# SCH_Display_Altium.net
KiCad netlist of a schematic drawn in Altium Designer
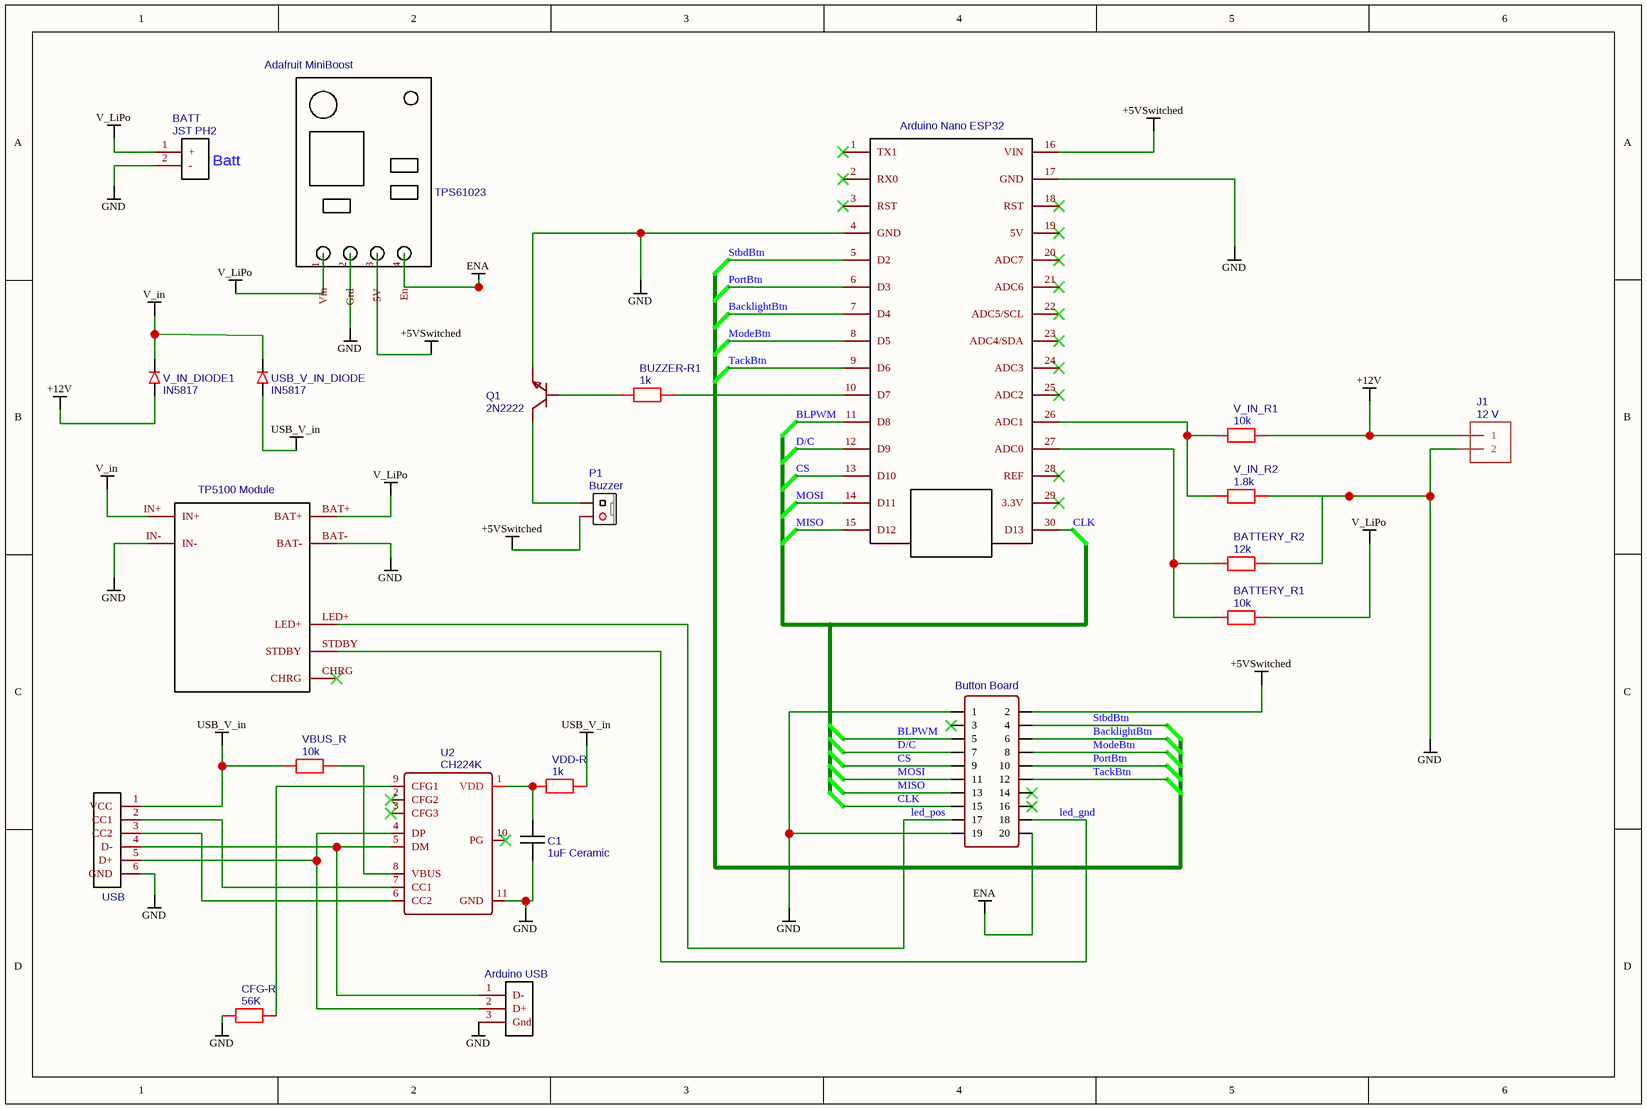
[diagram p0: SCH_Display_Altium.schdoc]

(export (version "E")
  (design (tool "Eeschema 10.0.6"))
  (components
    (comp (ref "BATT")
      (value "JST PH2")
      (fields (field (name "CONTRIBUTOR") "pwarrow99"))
      (libsource (lib "altium-import") (part "root_0_JST PH2_"))
    )
    (comp (ref "BATTERY_R1")
      (value "10k")
      (fields (field (name "CONTRIBUTOR") "Kagutsuchi"))
      (libsource (lib "altium-import") (part "root_0_10k_"))
    )
    (comp (ref "BATTERY_R2")
      (value "12k")
      (fields (field (name "CONTRIBUTOR") "Kagutsuchi"))
      (libsource (lib "altium-import") (part "root_0_12k_"))
    )
    (comp (ref "BUTTON_LED1")
      (value "Button Board")
      (fields (field (name "CONTRIBUTOR") "LCEDA_Lib"))
      (libsource (lib "altium-import") (part "root_0_Button Board_"))
    )
    (comp (ref "BUZZER-R1")
      (value "1k")
      (fields (field (name "CONTRIBUTOR") "Kagutsuchi"))
      (libsource (lib "altium-import") (part "root_0_1k_"))
    )
    (comp (ref "C1")
      (value "1uF Ceramic")
      (fields
        (field (name "MANUFACTURER PART") "Capacitor_Ceramic")
        (field (name "CONTRIBUTOR") "huuvinhz755")
      )
      (libsource (lib "altium-import") (part "root_3_1uF Ceramic_"))
    )
    (comp (ref "CFG-R")
      (value "56K")
      (fields (field (name "CONTRIBUTOR") "Kagutsuchi"))
      (libsource (lib "altium-import") (part "root_0_56K_"))
    )
    (comp (ref "J1")
      (value "12 V")
      (fields (field (name "CONTRIBUTOR") "Adafruit"))
      (libsource (lib "altium-import") (part "root_0_12 V_"))
    )
    (comp (ref "JST-PH-2.0_1X6")
      (value "USB")
      (fields (field (name "MANUFACTURER PART") "JST-PH-2.0_1x6") (field (name "CONTRIBUTOR") "yury26nev"))
      (libsource (lib "altium-import") (part "root_0_USB_"))
    )
    (comp (ref "JST_XH_1X3")
      (value "Arduino USB")
      (fields (field (name "CONTRIBUTOR") "GeMeMe"))
      (libsource (lib "altium-import") (part "root_0_Arduino USB_"))
    )
    (comp (ref "P1")
      (value "Buzzer")
      (fields
        (field (name "MANUFACTURER PART") "Headers  Pins2.54mm1*10P")
        (field (name "CONTRIBUTOR") "jousterde1")
      )
      (libsource (lib "altium-import") (part "root_0_Buzzer_"))
    )
    (comp (ref "Q1")
      (value "2N2222")
      (fields
        (field (name "MANUFACTURER") "ST(先科)")
        (field (name "MANUFACTURER PART") "2N2222A")
        (field (name "CONTRIBUTOR") "LCSC")
      )
      (libsource (lib "altium-import") (part "root_2_2N2222_"))
    )
    (comp (ref "TPS61023")
      (value "Adafruit MiniBoost")
      (fields (field (name "CONTRIBUTOR") "jefflorditch"))
      (libsource (lib "altium-import") (part "root_0_Adafruit MiniBoost_"))
    )
    (comp (ref "U1")
      (value "Arduino Nano ESP32")
      (fields (field (name "CONTRIBUTOR") "Nikolay Yanev"))
      (libsource (lib "altium-import") (part "root_0_Arduino Nano ESP32_"))
    )
    (comp (ref "U2")
      (value "CH224K")
      (fields (field (name "MANUFACTURER") "WCH(南京沁恒)") (field (name "CONTRIBUTOR") "lcsc"))
      (libsource (lib "altium-import") (part "root_0_CH224K_"))
    )
    (comp (ref "U3")
      (value "TP5100 Module")
      (fields (field (name "MANUFACTURER PART") "TP5100-MODULE") (field (name "CONTRIBUTOR") "cropemail"))
      (libsource (lib "altium-import") (part "root_0_TP5100 Module_"))
    )
    (comp (ref "USB_V_IN_DIODE")
      (value "IN5817")
      (fields (field (name "MANUFACTURER PART") "DIODE") (field (name "CONTRIBUTOR") "mimit.oscar"))
      (libsource (lib "altium-import") (part "root_1_IN5817_"))
    )
    (comp (ref "VBUS_R")
      (value "10k")
      (fields (field (name "CONTRIBUTOR") "Kagutsuchi"))
      (libsource (lib "altium-import") (part "root_0_10k_"))
    )
    (comp (ref "VDD-R")
      (value "1k")
      (fields (field (name "CONTRIBUTOR") "Kagutsuchi"))
      (libsource (lib "altium-import") (part "root_0_1k_"))
    )
    (comp (ref "V_IN_DIODE1")
      (value "IN5817")
      (fields (field (name "MANUFACTURER PART") "DIODE") (field (name "CONTRIBUTOR") "mimit.oscar"))
      (libsource (lib "altium-import") (part "root_1_IN5817_"))
    )
    (comp (ref "V_IN_R1")
      (value "10k")
      (fields (field (name "CONTRIBUTOR") "Kagutsuchi"))
      (libsource (lib "altium-import") (part "root_0_10k_"))
    )
    (comp (ref "V_IN_R2")
      (value "1.8k")
      (fields (field (name "CONTRIBUTOR") "Kagutsuchi"))
      (libsource (lib "altium-import") (part "root_0_1.8k_"))
    )
  )
  (nets
    (net (code "1") (name "+5VSwitched") (class "Default")
      (node (ref "BUTTON_LED1") (pin "2") (pinfunction "2_2") (pintype "passive"))
      (node (ref "P1") (pin "2") (pinfunction "2_2") (pintype "passive"))
      (node (ref "TPS61023") (pin "3") (pinfunction "5V_3") (pintype "passive"))
      (node (ref "U1") (pin "16") (pinfunction "VIN_16") (pintype "passive"))
    )
    (net (code "2") (name "+12V") (class "Default")
      (node (ref "J1") (pin "1") (pinfunction "1_1") (pintype "passive"))
      (node (ref "V_IN_DIODE1") (pin "1") (pinfunction "1_1") (pintype "passive"))
      (node (ref "V_IN_R1") (pin "2") (pinfunction "1_2") (pintype "passive"))
    )
    (net (code "3") (name "/BLPWM") (class "Default")
      (node (ref "BUTTON_LED1") (pin "5") (pinfunction "5_5") (pintype "passive"))
      (node (ref "U1") (pin "11") (pinfunction "D8_11") (pintype "passive"))
    )
    (net (code "4") (name "/BacklightBtn") (class "Default")
      (node (ref "BUTTON_LED1") (pin "6") (pinfunction "6_6") (pintype "passive"))
      (node (ref "U1") (pin "7") (pinfunction "D4_7") (pintype "passive"))
    )
    (net (code "5") (name "/CLK") (class "Default")
      (node (ref "BUTTON_LED1") (pin "15") (pinfunction "15_15") (pintype "passive"))
      (node (ref "U1") (pin "30") (pinfunction "D13_30") (pintype "passive"))
    )
    (net (code "6") (name "/CS") (class "Default")
      (node (ref "BUTTON_LED1") (pin "9") (pinfunction "9_9") (pintype "passive"))
      (node (ref "U1") (pin "13") (pinfunction "D10_13") (pintype "passive"))
    )
    (net (code "7") (name "/D{slash}C") (class "Default")
      (node (ref "BUTTON_LED1") (pin "7") (pinfunction "7_7") (pintype "passive"))
      (node (ref "U1") (pin "12") (pinfunction "D9_12") (pintype "passive"))
    )
    (net (code "8") (name "/MISO") (class "Default")
      (node (ref "BUTTON_LED1") (pin "13") (pinfunction "13_13") (pintype "passive"))
      (node (ref "U1") (pin "15") (pinfunction "D12_15") (pintype "passive"))
    )
    (net (code "9") (name "/MOSI") (class "Default")
      (node (ref "BUTTON_LED1") (pin "11") (pinfunction "11_11") (pintype "passive"))
      (node (ref "U1") (pin "14") (pinfunction "D11_14") (pintype "passive"))
    )
    (net (code "10") (name "/ModeBtn") (class "Default")
      (node (ref "BUTTON_LED1") (pin "8") (pinfunction "8_8") (pintype "passive"))
      (node (ref "U1") (pin "8") (pinfunction "D5_8") (pintype "passive"))
    )
    (net (code "11") (name "/PortBtn") (class "Default")
      (node (ref "BUTTON_LED1") (pin "10") (pinfunction "10_10") (pintype "passive"))
      (node (ref "U1") (pin "6") (pinfunction "D3_6") (pintype "passive"))
    )
    (net (code "12") (name "/StbdBtn") (class "Default")
      (node (ref "BUTTON_LED1") (pin "4") (pinfunction "4_4") (pintype "passive"))
      (node (ref "U1") (pin "5") (pinfunction "D2_5") (pintype "passive"))
    )
    (net (code "13") (name "/TackBtn") (class "Default")
      (node (ref "BUTTON_LED1") (pin "12") (pinfunction "12_12") (pintype "passive"))
      (node (ref "U1") (pin "9") (pinfunction "D6_9") (pintype "passive"))
    )
    (net (code "14") (name "/led_gnd") (class "Default")
      (node (ref "BUTTON_LED1") (pin "18") (pinfunction "18_18") (pintype "passive"))
      (node (ref "U3") (pin "STDBY") (pinfunction "STDBY_STDBY") (pintype "passive"))
    )
    (net (code "15") (name "/led_pos") (class "Default")
      (node (ref "BUTTON_LED1") (pin "17") (pinfunction "17_17") (pintype "passive"))
      (node (ref "U3") (pin "LED+") (pinfunction "LED+_LED+") (pintype "passive"))
    )
    (net (code "16") (name "ENA") (class "Default")
      (node (ref "BUTTON_LED1") (pin "20") (pinfunction "20_20") (pintype "passive"))
      (node (ref "TPS61023") (pin "4") (pinfunction "En_4") (pintype "passive"))
    )
    (net (code "17") (name "GND") (class "Default")
      (node (ref "BATT") (pin "2") (pinfunction "-_2") (pintype "passive"))
      (node (ref "BATTERY_R2") (pin "2") (pinfunction "1_2") (pintype "passive"))
      (node (ref "BUTTON_LED1") (pin "1") (pinfunction "1_1") (pintype "passive"))
      (node (ref "BUTTON_LED1") (pin "19") (pinfunction "19_19") (pintype "passive"))
      (node (ref "C1") (pin "2") (pinfunction "2_2") (pintype "passive"))
      (node (ref "CFG-R") (pin "1") (pinfunction "2_1") (pintype "passive"))
      (node (ref "J1") (pin "2") (pinfunction "2_2") (pintype "passive"))
      (node (ref "JST-PH-2.0_1X6") (pin "6") (pinfunction "GND_6") (pintype "passive"))
      (node (ref "JST_XH_1X3") (pin "3") (pinfunction "Gnd_3") (pintype "passive"))
      (node (ref "Q1") (pin "1") (pinfunction "E_1") (pintype "passive"))
      (node (ref "TPS61023") (pin "2") (pinfunction "Grd_2") (pintype "passive"))
      (node (ref "U1") (pin "17") (pinfunction "GND_17") (pintype "passive"))
      (node (ref "U1") (pin "4") (pinfunction "GND_4") (pintype "passive"))
      (node (ref "U2") (pin "11") (pinfunction "GND_11") (pintype "passive"))
      (node (ref "U3") (pin "BAT-") (pinfunction "BAT-_BAT-") (pintype "passive"))
      (node (ref "U3") (pin "IN-") (pinfunction "IN-_IN-") (pintype "passive"))
      (node (ref "V_IN_R2") (pin "2") (pinfunction "1_2") (pintype "passive"))
    )
    (net (code "18") (name "Net-(BATTERY_R1-2)") (class "Default")
      (node (ref "BATTERY_R1") (pin "1") (pinfunction "2_1") (pintype "passive"))
      (node (ref "BATTERY_R2") (pin "1") (pinfunction "2_1") (pintype "passive"))
      (node (ref "U1") (pin "27") (pinfunction "ADC0_27") (pintype "passive"))
    )
    (net (code "19") (name "Net-(BUZZER-R1-1)") (class "Default")
      (node (ref "BUZZER-R1") (pin "2") (pinfunction "1_2") (pintype "passive"))
      (node (ref "U1") (pin "10") (pinfunction "D7_10") (pintype "passive"))
    )
    (net (code "20") (name "Net-(BUZZER-R1-2)") (class "Default")
      (node (ref "BUZZER-R1") (pin "1") (pinfunction "2_1") (pintype "passive"))
      (node (ref "Q1") (pin "2") (pinfunction "B_2") (pintype "passive"))
    )
    (net (code "21") (name "Net-(CFG-R-1)") (class "Default")
      (node (ref "CFG-R") (pin "2") (pinfunction "1_2") (pintype "passive"))
      (node (ref "U2") (pin "9") (pinfunction "CFG1_9") (pintype "passive"))
    )
    (net (code "22") (name "Net-(JST-PH-2.0_1X6-CC1)") (class "Default")
      (node (ref "JST-PH-2.0_1X6") (pin "2") (pinfunction "CC1_2") (pintype "passive"))
      (node (ref "U2") (pin "7") (pinfunction "CC1_7") (pintype "passive"))
    )
    (net (code "23") (name "Net-(JST-PH-2.0_1X6-CC2)") (class "Default")
      (node (ref "JST-PH-2.0_1X6") (pin "3") (pinfunction "CC2_3") (pintype "passive"))
      (node (ref "U2") (pin "6") (pinfunction "CC2_6") (pintype "passive"))
    )
    (net (code "24") (name "Net-(JST-PH-2.0_1X6-D+)") (class "Default")
      (node (ref "JST-PH-2.0_1X6") (pin "5") (pinfunction "D+_5") (pintype "passive"))
      (node (ref "JST_XH_1X3") (pin "2") (pinfunction "D+_2") (pintype "passive"))
      (node (ref "U2") (pin "4") (pinfunction "DP_4") (pintype "passive"))
    )
    (net (code "25") (name "Net-(JST-PH-2.0_1X6-D-)") (class "Default")
      (node (ref "JST-PH-2.0_1X6") (pin "4") (pinfunction "D-_4") (pintype "passive"))
      (node (ref "JST_XH_1X3") (pin "1") (pinfunction "D-_1") (pintype "passive"))
      (node (ref "U2") (pin "5") (pinfunction "DM_5") (pintype "passive"))
    )
    (net (code "26") (name "Net-(Q1-C)") (class "Default")
      (node (ref "P1") (pin "1") (pinfunction "1_1") (pintype "passive"))
      (node (ref "Q1") (pin "3") (pinfunction "C_3") (pintype "passive"))
    )
    (net (code "27") (name "Net-(U1-ADC1)") (class "Default")
      (node (ref "U1") (pin "26") (pinfunction "ADC1_26") (pintype "passive"))
      (node (ref "V_IN_R1") (pin "1") (pinfunction "2_1") (pintype "passive"))
      (node (ref "V_IN_R2") (pin "1") (pinfunction "2_1") (pintype "passive"))
    )
    (net (code "28") (name "Net-(U2-VBUS)") (class "Default")
      (node (ref "U2") (pin "8") (pinfunction "VBUS_8") (pintype "passive"))
      (node (ref "VBUS_R") (pin "2") (pinfunction "1_2") (pintype "passive"))
    )
    (net (code "29") (name "Net-(U2-VDD)") (class "Default")
      (node (ref "C1") (pin "1") (pinfunction "1_1") (pintype "passive"))
      (node (ref "U2") (pin "1") (pinfunction "VDD_1") (pintype "passive"))
      (node (ref "VDD-R") (pin "1") (pinfunction "2_1") (pintype "passive"))
    )
    (net (code "30") (name "USB_V_in") (class "Default")
      (node (ref "JST-PH-2.0_1X6") (pin "1") (pinfunction "VCC_1") (pintype "passive"))
      (node (ref "USB_V_IN_DIODE") (pin "1") (pinfunction "1_1") (pintype "passive"))
      (node (ref "VBUS_R") (pin "1") (pinfunction "2_1") (pintype "passive"))
      (node (ref "VDD-R") (pin "2") (pinfunction "1_2") (pintype "passive"))
    )
    (net (code "31") (name "V_LiPo") (class "Default")
      (node (ref "BATT") (pin "1") (pinfunction "+_1") (pintype "passive"))
      (node (ref "BATTERY_R1") (pin "2") (pinfunction "1_2") (pintype "passive"))
      (node (ref "TPS61023") (pin "1") (pinfunction "Vin_1") (pintype "passive"))
      (node (ref "U3") (pin "BAT+") (pinfunction "BAT+_BAT+") (pintype "passive"))
    )
    (net (code "32") (name "V_in") (class "Default")
      (node (ref "U3") (pin "IN+") (pinfunction "IN+_IN+") (pintype "passive"))
      (node (ref "USB_V_IN_DIODE") (pin "2") (pinfunction "2_2") (pintype "passive"))
      (node (ref "V_IN_DIODE1") (pin "2") (pinfunction "2_2") (pintype "passive"))
    )
    (net (code "33") (name "unconnected-(BUTTON_LED1-Pad3)") (class "Default")
      (node (ref "BUTTON_LED1") (pin "3") (pinfunction "3_3") (pintype "passive+no_connect"))
    )
    (net (code "34") (name "unconnected-(BUTTON_LED1-Pad14)") (class "Default")
      (node (ref "BUTTON_LED1") (pin "14") (pinfunction "14_14") (pintype "passive+no_connect"))
    )
    (net (code "35") (name "unconnected-(BUTTON_LED1-Pad16)") (class "Default")
      (node (ref "BUTTON_LED1") (pin "16") (pinfunction "16_16") (pintype "passive+no_connect"))
    )
    (net (code "36") (name "unconnected-(U1-3.3V-Pad29)") (class "Default")
      (node (ref "U1") (pin "29") (pinfunction "3.3V_29") (pintype "passive+no_connect"))
    )
    (net (code "37") (name "unconnected-(U1-5V-Pad19)") (class "Default")
      (node (ref "U1") (pin "19") (pinfunction "5V_19") (pintype "passive+no_connect"))
    )
    (net (code "38") (name "unconnected-(U1-ADC2-Pad25)") (class "Default")
      (node (ref "U1") (pin "25") (pinfunction "ADC2_25") (pintype "passive+no_connect"))
    )
    (net (code "39") (name "unconnected-(U1-ADC3-Pad24)") (class "Default")
      (node (ref "U1") (pin "24") (pinfunction "ADC3_24") (pintype "passive+no_connect"))
    )
    (net (code "40") (name "unconnected-(U1-ADC4{slash}SDA-Pad23)") (class "Default")
      (node (ref "U1") (pin "23") (pinfunction "ADC4/SDA_23") (pintype "passive+no_connect"))
    )
    (net (code "41") (name "unconnected-(U1-ADC5{slash}SCL-Pad22)") (class "Default")
      (node (ref "U1") (pin "22") (pinfunction "ADC5/SCL_22") (pintype "passive+no_connect"))
    )
    (net (code "42") (name "unconnected-(U1-ADC6-Pad21)") (class "Default")
      (node (ref "U1") (pin "21") (pinfunction "ADC6_21") (pintype "passive+no_connect"))
    )
    (net (code "43") (name "unconnected-(U1-ADC7-Pad20)") (class "Default")
      (node (ref "U1") (pin "20") (pinfunction "ADC7_20") (pintype "passive+no_connect"))
    )
    (net (code "44") (name "unconnected-(U1-REF-Pad28)") (class "Default")
      (node (ref "U1") (pin "28") (pinfunction "REF_28") (pintype "passive+no_connect"))
    )
    (net (code "45") (name "unconnected-(U1-RST-Pad3)") (class "Default")
      (node (ref "U1") (pin "3") (pinfunction "RST_3") (pintype "passive+no_connect"))
    )
    (net (code "46") (name "unconnected-(U1-RST-Pad18)") (class "Default")
      (node (ref "U1") (pin "18") (pinfunction "RST_18") (pintype "passive+no_connect"))
    )
    (net (code "47") (name "unconnected-(U1-RX0-Pad2)") (class "Default")
      (node (ref "U1") (pin "2") (pinfunction "RX0_2") (pintype "passive+no_connect"))
    )
    (net (code "48") (name "unconnected-(U1-TX1-Pad1)") (class "Default")
      (node (ref "U1") (pin "1") (pinfunction "TX1_1") (pintype "passive+no_connect"))
    )
    (net (code "49") (name "unconnected-(U2-CFG2-Pad2)") (class "Default")
      (node (ref "U2") (pin "2") (pinfunction "CFG2_2") (pintype "passive+no_connect"))
    )
    (net (code "50") (name "unconnected-(U2-CFG3-Pad3)") (class "Default")
      (node (ref "U2") (pin "3") (pinfunction "CFG3_3") (pintype "passive+no_connect"))
    )
    (net (code "51") (name "unconnected-(U2-PG-Pad10)") (class "Default")
      (node (ref "U2") (pin "10") (pinfunction "PG_10") (pintype "passive+no_connect"))
    )
    (net (code "52") (name "unconnected-(U3-PadCHRG)") (class "Default")
      (node (ref "U3") (pin "CHRG") (pinfunction "CHRG_CHRG") (pintype "passive+no_connect"))
    )
  )
)
